# CM_FPGA_B2-3.net
KiCad netlist of a schematic drawn in Altium Designer
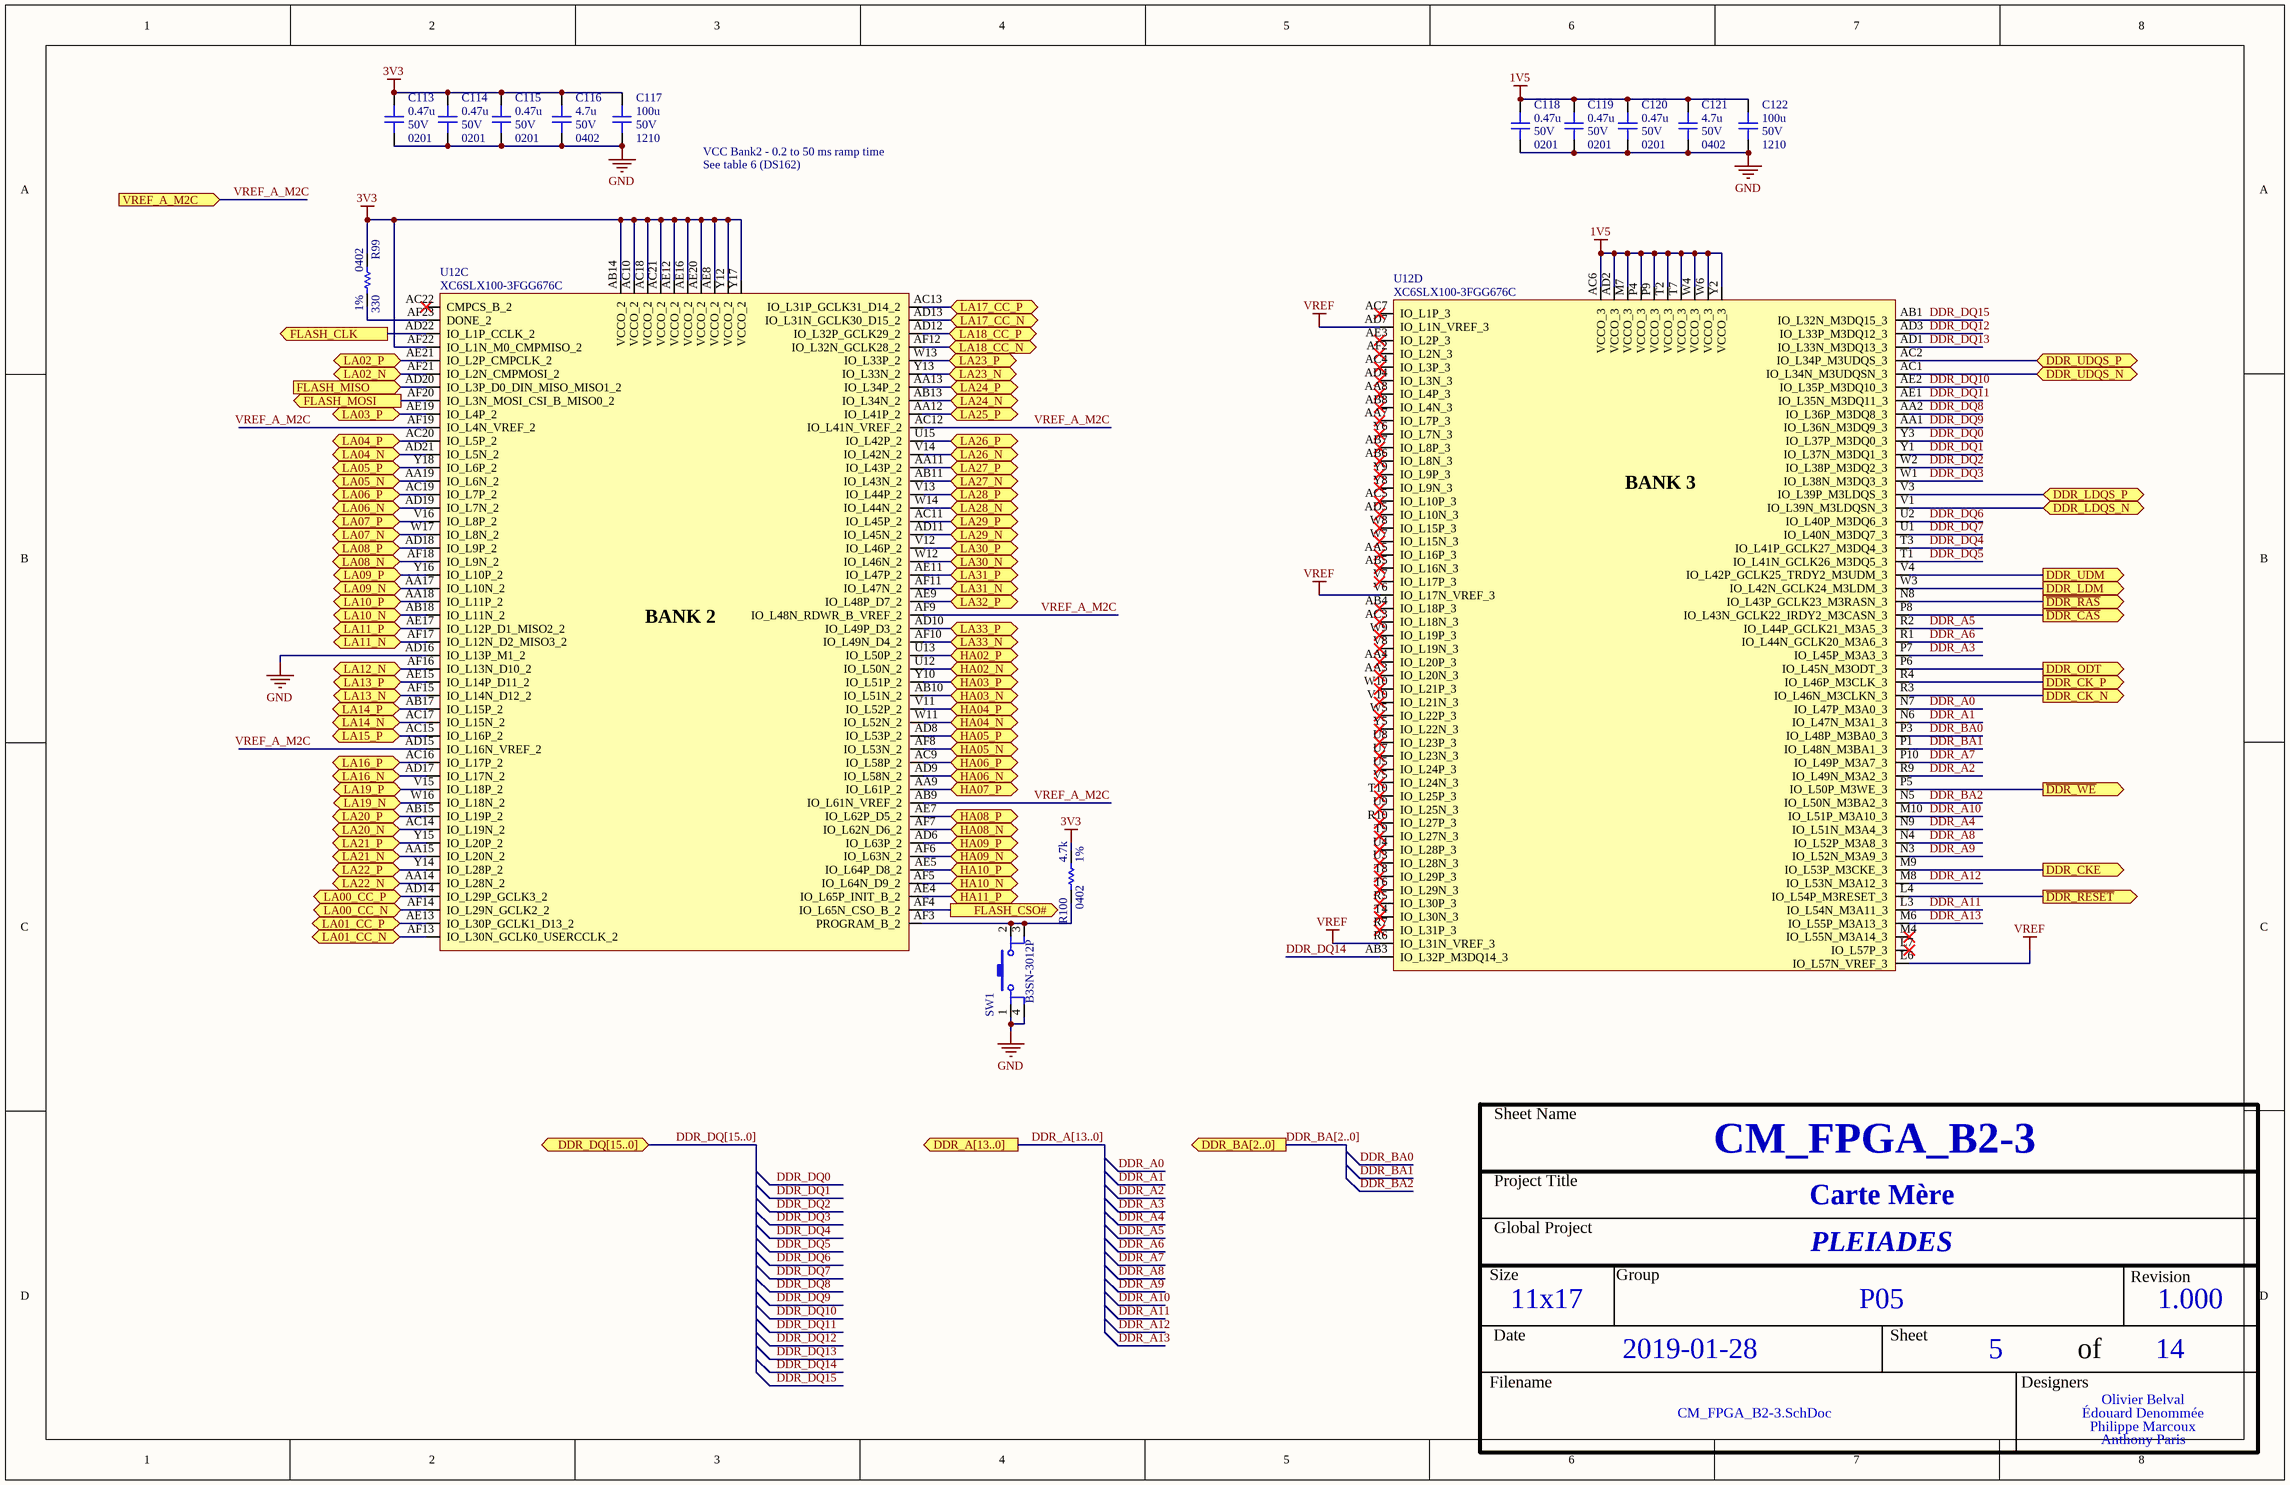
[diagram p0: CM_FPGA_B2-3.SchDoc]

(export (version "E")
  (design (tool "Eeschema 10.0.6"))
  (components
    (comp (ref "C113")
      (value "0.47u")
      (footprint "CAP_0201")
      (description "CAP - 0201")
      (fields
        (field (name "VOLTAGE") "50V")
        (field (name "PACKAGE") "0201")
        (field (name "CREATEDBY") "Jonathan Bouchard")
      )
      (libsource (lib "S7CAS_Lib2019_REV1_00") (part "CAP - 0201"))
    )
    (comp (ref "C114")
      (value "0.47u")
      (footprint "CAP_0201")
      (description "CAP - 0201")
      (fields
        (field (name "VOLTAGE") "50V")
        (field (name "PACKAGE") "0201")
        (field (name "CREATEDBY") "Jonathan Bouchard")
      )
      (libsource (lib "S7CAS_Lib2019_REV1_00") (part "CAP - 0201"))
    )
    (comp (ref "C115")
      (value "0.47u")
      (footprint "CAP_0201")
      (description "CAP - 0201")
      (fields
        (field (name "VOLTAGE") "50V")
        (field (name "PACKAGE") "0201")
        (field (name "CREATEDBY") "Jonathan Bouchard")
      )
      (libsource (lib "S7CAS_Lib2019_REV1_00") (part "CAP - 0201"))
    )
    (comp (ref "C116")
      (value "4.7u")
      (footprint "CAP_0402")
      (description "CAP - 0402")
      (fields
        (field (name "VOLTAGE") "50V")
        (field (name "PACKAGE") "0402")
        (field (name "CREATEDBY") "Jonathan Bouchard")
      )
      (libsource (lib "S7CAS_Lib2019_REV1_00") (part "CAP - 0402"))
    )
    (comp (ref "C117")
      (value "100u")
      (footprint "CAP_1210")
      (description "CAP - 1210")
      (fields
        (field (name "VOLTAGE") "50V")
        (field (name "PACKAGE") "1210")
        (field (name "CREATEDBY") "Jonathan Bouchard")
      )
      (libsource (lib "S7CAS_Lib2019_REV1_00") (part "CAP - 1210"))
    )
    (comp (ref "C118")
      (value "0.47u")
      (footprint "CAP_0201")
      (description "CAP - 0201")
      (fields
        (field (name "VOLTAGE") "50V")
        (field (name "PACKAGE") "0201")
        (field (name "CREATEDBY") "Jonathan Bouchard")
      )
      (libsource (lib "S7CAS_Lib2019_REV1_00") (part "CAP - 0201"))
    )
    (comp (ref "C119")
      (value "0.47u")
      (footprint "CAP_0201")
      (description "CAP - 0201")
      (fields
        (field (name "VOLTAGE") "50V")
        (field (name "PACKAGE") "0201")
        (field (name "CREATEDBY") "Jonathan Bouchard")
      )
      (libsource (lib "S7CAS_Lib2019_REV1_00") (part "CAP - 0201"))
    )
    (comp (ref "C120")
      (value "0.47u")
      (footprint "CAP_0201")
      (description "CAP - 0201")
      (fields
        (field (name "VOLTAGE") "50V")
        (field (name "PACKAGE") "0201")
        (field (name "CREATEDBY") "Jonathan Bouchard")
      )
      (libsource (lib "S7CAS_Lib2019_REV1_00") (part "CAP - 0201"))
    )
    (comp (ref "C121")
      (value "4.7u")
      (footprint "CAP_0402")
      (description "CAP - 0402")
      (fields
        (field (name "VOLTAGE") "50V")
        (field (name "PACKAGE") "0402")
        (field (name "CREATEDBY") "Jonathan Bouchard")
      )
      (libsource (lib "S7CAS_Lib2019_REV1_00") (part "CAP - 0402"))
    )
    (comp (ref "C122")
      (value "100u")
      (footprint "CAP_1210")
      (description "CAP - 1210")
      (fields
        (field (name "VOLTAGE") "50V")
        (field (name "PACKAGE") "1210")
        (field (name "CREATEDBY") "Jonathan Bouchard")
      )
      (libsource (lib "S7CAS_Lib2019_REV1_00") (part "CAP - 1210"))
    )
    (comp (ref "R99")
      (value "330")
      (footprint "RES_0402")
      (description "RES - 0402")
      (fields
        (field (name "VOLTAGE") "50V")
        (field (name "POWER") "1/16W")
        (field (name "PACKAGE") "0402")
        (field (name "PRECISION") "1%")
        (field (name "CREATEDBY") "Jonathan Bouchard")
      )
      (libsource (lib "S7CAS_Lib2019_REV1_00") (part "RES - 0402"))
    )
    (comp (ref "R100")
      (value "4.7k")
      (footprint "RES_0402")
      (description "RES - 0402")
      (fields
        (field (name "VOLTAGE") "50V")
        (field (name "POWER") "1/16W")
        (field (name "PACKAGE") "0402")
        (field (name "PRECISION") "1%")
        (field (name "CREATEDBY") "Jonathan Bouchard")
      )
      (libsource (lib "S7CAS_Lib2019_REV1_00") (part "RES - 0402"))
    )
    (comp (ref "SW1")
      (value "B3SN-3012P")
      (footprint "SWI_TACT_B3SN-3012P")
      (description "SWI - TACT SPST-NO 0.05A 24V - 4-SMD")
      (fields
        (field (name "MFG") "Omron")
        (field (name "VOLTAGE") "24V")
        (field (name "CREATEDBY") "Jonathan Bouchard")
      )
      (libsource (lib "S7CAS_Lib2019_REV1_00") (part "SWI_TACT_B3SN-3012P"))
    )
    (comp (ref "U12")
      (value "XC6SLX100-3FGG676C")
      (footprint "FPGA_XILINX_FGG676")
      (description "FPGA - XILINX SPARTAN 6 480 I/O - BGA-676")
      (fields
        (field (name "VOLTAGE") "1.14 V ~ 1.26 V")
        (field (name "MFG") "Xilinx")
        (field (name "CREATEDBY") "Jonathan Bouchard")
      )
      (libsource (lib "S7CAS_Lib2019_REV1_00") (part "FPGA_XC6SLX100-3FGG676C"))
    )
  )
  (nets
    (net (code "1") (name "/DDR_A0") (class "Default")
      (node (ref "U12") (pin "N7") (pinfunction "IO_L47P_M3A0_3_N7") (pintype "passive"))
    )
    (net (code "2") (name "/DDR_A1") (class "Default")
      (node (ref "U12") (pin "N6") (pinfunction "IO_L47N_M3A1_3_N6") (pintype "passive"))
    )
    (net (code "3") (name "/DDR_A2") (class "Default")
      (node (ref "U12") (pin "R9") (pinfunction "IO_L49N_M3A2_3_R9") (pintype "passive"))
    )
    (net (code "4") (name "/DDR_A3") (class "Default")
      (node (ref "U12") (pin "P7") (pinfunction "IO_L45P_M3A3_3_P7") (pintype "passive"))
    )
    (net (code "5") (name "/DDR_A4") (class "Default")
      (node (ref "U12") (pin "N9") (pinfunction "IO_L51N_M3A4_3_N9") (pintype "passive"))
    )
    (net (code "6") (name "/DDR_A5") (class "Default")
      (node (ref "U12") (pin "R2") (pinfunction "IO_L44P_GCLK21_M3A5_3_R2") (pintype "passive"))
    )
    (net (code "7") (name "/DDR_A6") (class "Default")
      (node (ref "U12") (pin "R1") (pinfunction "IO_L44N_GCLK20_M3A6_3_R1") (pintype "passive"))
    )
    (net (code "8") (name "/DDR_A7") (class "Default")
      (node (ref "U12") (pin "P10") (pinfunction "IO_L49P_M3A7_3_P10") (pintype "passive"))
    )
    (net (code "9") (name "/DDR_A8") (class "Default")
      (node (ref "U12") (pin "N4") (pinfunction "IO_L52P_M3A8_3_N4") (pintype "passive"))
    )
    (net (code "10") (name "/DDR_A9") (class "Default")
      (node (ref "U12") (pin "N3") (pinfunction "IO_L52N_M3A9_3_N3") (pintype "passive"))
    )
    (net (code "11") (name "/DDR_A10") (class "Default")
      (node (ref "U12") (pin "M10") (pinfunction "IO_L51P_M3A10_3_M10") (pintype "passive"))
    )
    (net (code "12") (name "/DDR_A11") (class "Default")
      (node (ref "U12") (pin "L3") (pinfunction "IO_L54N_M3A11_3_L3") (pintype "passive"))
    )
    (net (code "13") (name "/DDR_A12") (class "Default")
      (node (ref "U12") (pin "M8") (pinfunction "IO_L53N_M3A12_3_M8") (pintype "passive"))
    )
    (net (code "14") (name "/DDR_A13") (class "Default")
      (node (ref "U12") (pin "M6") (pinfunction "IO_L55P_M3A13_3_M6") (pintype "passive"))
    )
    (net (code "16") (name "/DDR_BA0") (class "Default")
      (node (ref "U12") (pin "P3") (pinfunction "IO_L48P_M3BA0_3_P3") (pintype "passive"))
    )
    (net (code "17") (name "/DDR_BA1") (class "Default")
      (node (ref "U12") (pin "P1") (pinfunction "IO_L48N_M3BA1_3_P1") (pintype "passive"))
    )
    (net (code "18") (name "/DDR_BA2") (class "Default")
      (node (ref "U12") (pin "N5") (pinfunction "IO_L50N_M3BA2_3_N5") (pintype "passive"))
    )
    (net (code "20") (name "/DDR_CAS") (class "Default")
      (node (ref "U12") (pin "P8") (pinfunction "IO_L43N_GCLK22_IRDY2_M3CASN_3_P8") (pintype "passive"))
    )
    (net (code "21") (name "/DDR_CKE") (class "Default")
      (node (ref "U12") (pin "M9") (pinfunction "IO_L53P_M3CKE_3_M9") (pintype "passive"))
    )
    (net (code "22") (name "/DDR_CK_N") (class "Default")
      (node (ref "U12") (pin "R3") (pinfunction "IO_L46N_M3CLKN_3_R3") (pintype "passive"))
    )
    (net (code "23") (name "/DDR_CK_P") (class "Default")
      (node (ref "U12") (pin "R4") (pinfunction "IO_L46P_M3CLK_3_R4") (pintype "passive"))
    )
    (net (code "24") (name "/DDR_DQ0") (class "Default")
      (node (ref "U12") (pin "Y3") (pinfunction "IO_L37P_M3DQ0_3_Y3") (pintype "passive"))
    )
    (net (code "25") (name "/DDR_DQ1") (class "Default")
      (node (ref "U12") (pin "Y1") (pinfunction "IO_L37N_M3DQ1_3_Y1") (pintype "passive"))
    )
    (net (code "26") (name "/DDR_DQ2") (class "Default")
      (node (ref "U12") (pin "W2") (pinfunction "IO_L38P_M3DQ2_3_W2") (pintype "passive"))
    )
    (net (code "27") (name "/DDR_DQ3") (class "Default")
      (node (ref "U12") (pin "W1") (pinfunction "IO_L38N_M3DQ3_3_W1") (pintype "passive"))
    )
    (net (code "28") (name "/DDR_DQ4") (class "Default")
      (node (ref "U12") (pin "T3") (pinfunction "IO_L41P_GCLK27_M3DQ4_3_T3") (pintype "passive"))
    )
    (net (code "29") (name "/DDR_DQ5") (class "Default")
      (node (ref "U12") (pin "T1") (pinfunction "IO_L41N_GCLK26_M3DQ5_3_T1") (pintype "passive"))
    )
    (net (code "30") (name "/DDR_DQ6") (class "Default")
      (node (ref "U12") (pin "U2") (pinfunction "IO_L40P_M3DQ6_3_U2") (pintype "passive"))
    )
    (net (code "31") (name "/DDR_DQ7") (class "Default")
      (node (ref "U12") (pin "U1") (pinfunction "IO_L40N_M3DQ7_3_U1") (pintype "passive"))
    )
    (net (code "32") (name "/DDR_DQ8") (class "Default")
      (node (ref "U12") (pin "AA2") (pinfunction "IO_L36P_M3DQ8_3_AA2") (pintype "passive"))
    )
    (net (code "33") (name "/DDR_DQ9") (class "Default")
      (node (ref "U12") (pin "AA1") (pinfunction "IO_L36N_M3DQ9_3_AA1") (pintype "passive"))
    )
    (net (code "34") (name "/DDR_DQ10") (class "Default")
      (node (ref "U12") (pin "AE2") (pinfunction "IO_L35P_M3DQ10_3_AE2") (pintype "passive"))
    )
    (net (code "35") (name "/DDR_DQ11") (class "Default")
      (node (ref "U12") (pin "AE1") (pinfunction "IO_L35N_M3DQ11_3_AE1") (pintype "passive"))
    )
    (net (code "36") (name "/DDR_DQ12") (class "Default")
      (node (ref "U12") (pin "AD3") (pinfunction "IO_L33P_M3DQ12_3_AD3") (pintype "passive"))
    )
    (net (code "37") (name "/DDR_DQ13") (class "Default")
      (node (ref "U12") (pin "AD1") (pinfunction "IO_L33N_M3DQ13_3_AD1") (pintype "passive"))
    )
    (net (code "38") (name "/DDR_DQ14") (class "Default")
      (node (ref "U12") (pin "AB3") (pinfunction "IO_L32P_M3DQ14_3_AB3") (pintype "passive"))
    )
    (net (code "39") (name "/DDR_DQ15") (class "Default")
      (node (ref "U12") (pin "AB1") (pinfunction "IO_L32N_M3DQ15_3_AB1") (pintype "passive"))
    )
    (net (code "41") (name "/DDR_LDM") (class "Default")
      (node (ref "U12") (pin "W3") (pinfunction "IO_L42N_GCLK24_M3LDM_3_W3") (pintype "passive"))
    )
    (net (code "42") (name "/DDR_LDQS_N") (class "Default")
      (node (ref "U12") (pin "V1") (pinfunction "IO_L39N_M3LDQSN_3_V1") (pintype "passive"))
    )
    (net (code "43") (name "/DDR_LDQS_P") (class "Default")
      (node (ref "U12") (pin "V3") (pinfunction "IO_L39P_M3LDQS_3_V3") (pintype "passive"))
    )
    (net (code "44") (name "/DDR_ODT") (class "Default")
      (node (ref "U12") (pin "P6") (pinfunction "IO_L45N_M3ODT_3_P6") (pintype "passive"))
    )
    (net (code "45") (name "/DDR_RAS") (class "Default")
      (node (ref "U12") (pin "N8") (pinfunction "IO_L43P_GCLK23_M3RASN_3_N8") (pintype "passive"))
    )
    (net (code "46") (name "/DDR_RESET") (class "Default")
      (node (ref "U12") (pin "L4") (pinfunction "IO_L54P_M3RESET_3_L4") (pintype "passive"))
    )
    (net (code "47") (name "/DDR_UDM") (class "Default")
      (node (ref "U12") (pin "V4") (pinfunction "IO_L42P_GCLK25_TRDY2_M3UDM_3_V4") (pintype "passive"))
    )
    (net (code "48") (name "/DDR_UDQS_N") (class "Default")
      (node (ref "U12") (pin "AC1") (pinfunction "IO_L34N_M3UDQSN_3_AC1") (pintype "passive"))
    )
    (net (code "49") (name "/DDR_UDQS_P") (class "Default")
      (node (ref "U12") (pin "AC2") (pinfunction "IO_L34P_M3UDQS_3_AC2") (pintype "passive"))
    )
    (net (code "50") (name "/DDR_WE") (class "Default")
      (node (ref "U12") (pin "P5") (pinfunction "IO_L50P_M3WE_3_P5") (pintype "passive"))
    )
    (net (code "51") (name "/FLASH_CLK") (class "Default")
      (node (ref "U12") (pin "AD22") (pinfunction "IO_L1P_CCLK_2_AD22") (pintype "passive"))
    )
    (net (code "52") (name "/FLASH_CSO#") (class "Default")
      (node (ref "U12") (pin "AF4") (pinfunction "IO_L65N_CSO_B_2_AF4") (pintype "passive"))
    )
    (net (code "53") (name "/FLASH_MISO") (class "Default")
      (node (ref "U12") (pin "AD20") (pinfunction "IO_L3P_D0_DIN_MISO_MISO1_2_AD20") (pintype "passive"))
    )
    (net (code "54") (name "/FLASH_MOSI") (class "Default")
      (node (ref "U12") (pin "AF20") (pinfunction "IO_L3N_MOSI_CSI_B_MISO0_2_AF20") (pintype "passive"))
    )
    (net (code "55") (name "/HA02_N") (class "Default")
      (node (ref "U12") (pin "U12") (pinfunction "IO_L50N_2_U12") (pintype "passive"))
    )
    (net (code "56") (name "/HA02_P") (class "Default")
      (node (ref "U12") (pin "U13") (pinfunction "IO_L50P_2_U13") (pintype "passive"))
    )
    (net (code "57") (name "/HA03_N") (class "Default")
      (node (ref "U12") (pin "AB10") (pinfunction "IO_L51N_2_AB10") (pintype "passive"))
    )
    (net (code "58") (name "/HA03_P") (class "Default")
      (node (ref "U12") (pin "Y10") (pinfunction "IO_L51P_2_Y10") (pintype "passive"))
    )
    (net (code "59") (name "/HA04_N") (class "Default")
      (node (ref "U12") (pin "W11") (pinfunction "IO_L52N_2_W11") (pintype "passive"))
    )
    (net (code "60") (name "/HA04_P") (class "Default")
      (node (ref "U12") (pin "V11") (pinfunction "IO_L52P_2_V11") (pintype "passive"))
    )
    (net (code "61") (name "/HA05_N") (class "Default")
      (node (ref "U12") (pin "AF8") (pinfunction "IO_L53N_2_AF8") (pintype "passive"))
    )
    (net (code "62") (name "/HA05_P") (class "Default")
      (node (ref "U12") (pin "AD8") (pinfunction "IO_L53P_2_AD8") (pintype "passive"))
    )
    (net (code "63") (name "/HA06_N") (class "Default")
      (node (ref "U12") (pin "AD9") (pinfunction "IO_L58N_2_AD9") (pintype "passive"))
    )
    (net (code "64") (name "/HA06_P") (class "Default")
      (node (ref "U12") (pin "AC9") (pinfunction "IO_L58P_2_AC9") (pintype "passive"))
    )
    (net (code "65") (name "/HA07_P") (class "Default")
      (node (ref "U12") (pin "AA9") (pinfunction "IO_L61P_2_AA9") (pintype "passive"))
    )
    (net (code "66") (name "/HA08_N") (class "Default")
      (node (ref "U12") (pin "AF7") (pinfunction "IO_L62N_D6_2_AF7") (pintype "passive"))
    )
    (net (code "67") (name "/HA08_P") (class "Default")
      (node (ref "U12") (pin "AE7") (pinfunction "IO_L62P_D5_2_AE7") (pintype "passive"))
    )
    (net (code "68") (name "/HA09_N") (class "Default")
      (node (ref "U12") (pin "AF6") (pinfunction "IO_L63N_2_AF6") (pintype "passive"))
    )
    (net (code "69") (name "/HA09_P") (class "Default")
      (node (ref "U12") (pin "AD6") (pinfunction "IO_L63P_2_AD6") (pintype "passive"))
    )
    (net (code "70") (name "/HA10_N") (class "Default")
      (node (ref "U12") (pin "AF5") (pinfunction "IO_L64N_D9_2_AF5") (pintype "passive"))
    )
    (net (code "71") (name "/HA10_P") (class "Default")
      (node (ref "U12") (pin "AE5") (pinfunction "IO_L64P_D8_2_AE5") (pintype "passive"))
    )
    (net (code "72") (name "/HA11_P") (class "Default")
      (node (ref "U12") (pin "AE4") (pinfunction "IO_L65P_INIT_B_2_AE4") (pintype "passive"))
    )
    (net (code "73") (name "/LA00_CC_N") (class "Default")
      (node (ref "U12") (pin "AF14") (pinfunction "IO_L29N_GCLK2_2_AF14") (pintype "passive"))
    )
    (net (code "74") (name "/LA00_CC_P") (class "Default")
      (node (ref "U12") (pin "AD14") (pinfunction "IO_L29P_GCLK3_2_AD14") (pintype "passive"))
    )
    (net (code "75") (name "/LA01_CC_N") (class "Default")
      (node (ref "U12") (pin "AF13") (pinfunction "IO_L30N_GCLK0_USERCCLK_2_AF13") (pintype "passive"))
    )
    (net (code "76") (name "/LA01_CC_P") (class "Default")
      (node (ref "U12") (pin "AE13") (pinfunction "IO_L30P_GCLK1_D13_2_AE13") (pintype "passive"))
    )
    (net (code "77") (name "/LA02_N") (class "Default")
      (node (ref "U12") (pin "AF21") (pinfunction "IO_L2N_CMPMOSI_2_AF21") (pintype "passive"))
    )
    (net (code "78") (name "/LA02_P") (class "Default")
      (node (ref "U12") (pin "AE21") (pinfunction "IO_L2P_CMPCLK_2_AE21") (pintype "passive"))
    )
    (net (code "79") (name "/LA03_P") (class "Default")
      (node (ref "U12") (pin "AE19") (pinfunction "IO_L4P_2_AE19") (pintype "passive"))
    )
    (net (code "80") (name "/LA04_N") (class "Default")
      (node (ref "U12") (pin "AD21") (pinfunction "IO_L5N_2_AD21") (pintype "passive"))
    )
    (net (code "81") (name "/LA04_P") (class "Default")
      (node (ref "U12") (pin "AC20") (pinfunction "IO_L5P_2_AC20") (pintype "passive"))
    )
    (net (code "82") (name "/LA05_N") (class "Default")
      (node (ref "U12") (pin "AA19") (pinfunction "IO_L6N_2_AA19") (pintype "passive"))
    )
    (net (code "83") (name "/LA05_P") (class "Default")
      (node (ref "U12") (pin "Y18") (pinfunction "IO_L6P_2_Y18") (pintype "passive"))
    )
    (net (code "84") (name "/LA06_N") (class "Default")
      (node (ref "U12") (pin "AD19") (pinfunction "IO_L7N_2_AD19") (pintype "passive"))
    )
    (net (code "85") (name "/LA06_P") (class "Default")
      (node (ref "U12") (pin "AC19") (pinfunction "IO_L7P_2_AC19") (pintype "passive"))
    )
    (net (code "86") (name "/LA07_N") (class "Default")
      (node (ref "U12") (pin "W17") (pinfunction "IO_L8N_2_W17") (pintype "passive"))
    )
    (net (code "87") (name "/LA07_P") (class "Default")
      (node (ref "U12") (pin "V16") (pinfunction "IO_L8P_2_V16") (pintype "passive"))
    )
    (net (code "88") (name "/LA08_N") (class "Default")
      (node (ref "U12") (pin "AF18") (pinfunction "IO_L9N_2_AF18") (pintype "passive"))
    )
    (net (code "89") (name "/LA08_P") (class "Default")
      (node (ref "U12") (pin "AD18") (pinfunction "IO_L9P_2_AD18") (pintype "passive"))
    )
    (net (code "90") (name "/LA09_N") (class "Default")
      (node (ref "U12") (pin "AA17") (pinfunction "IO_L10N_2_AA17") (pintype "passive"))
    )
    (net (code "91") (name "/LA09_P") (class "Default")
      (node (ref "U12") (pin "Y16") (pinfunction "IO_L10P_2_Y16") (pintype "passive"))
    )
    (net (code "92") (name "/LA10_N") (class "Default")
      (node (ref "U12") (pin "AB18") (pinfunction "IO_L11N_2_AB18") (pintype "passive"))
    )
    (net (code "93") (name "/LA10_P") (class "Default")
      (node (ref "U12") (pin "AA18") (pinfunction "IO_L11P_2_AA18") (pintype "passive"))
    )
    (net (code "94") (name "/LA11_N") (class "Default")
      (node (ref "U12") (pin "AF17") (pinfunction "IO_L12N_D2_MISO3_2_AF17") (pintype "passive"))
    )
    (net (code "95") (name "/LA11_P") (class "Default")
      (node (ref "U12") (pin "AE17") (pinfunction "IO_L12P_D1_MISO2_2_AE17") (pintype "passive"))
    )
    (net (code "96") (name "/LA12_N") (class "Default")
      (node (ref "U12") (pin "AF16") (pinfunction "IO_L13N_D10_2_AF16") (pintype "passive"))
    )
    (net (code "97") (name "/LA13_N") (class "Default")
      (node (ref "U12") (pin "AF15") (pinfunction "IO_L14N_D12_2_AF15") (pintype "passive"))
    )
    (net (code "98") (name "/LA13_P") (class "Default")
      (node (ref "U12") (pin "AE15") (pinfunction "IO_L14P_D11_2_AE15") (pintype "passive"))
    )
    (net (code "99") (name "/LA14_N") (class "Default")
      (node (ref "U12") (pin "AC17") (pinfunction "IO_L15N_2_AC17") (pintype "passive"))
    )
    (net (code "100") (name "/LA14_P") (class "Default")
      (node (ref "U12") (pin "AB17") (pinfunction "IO_L15P_2_AB17") (pintype "passive"))
    )
    (net (code "101") (name "/LA15_P") (class "Default")
      (node (ref "U12") (pin "AC15") (pinfunction "IO_L16P_2_AC15") (pintype "passive"))
    )
    (net (code "102") (name "/LA16_N") (class "Default")
      (node (ref "U12") (pin "AD17") (pinfunction "IO_L17N_2_AD17") (pintype "passive"))
    )
    (net (code "103") (name "/LA16_P") (class "Default")
      (node (ref "U12") (pin "AC16") (pinfunction "IO_L17P_2_AC16") (pintype "passive"))
    )
    (net (code "104") (name "/LA17_CC_N") (class "Default")
      (node (ref "U12") (pin "AD13") (pinfunction "IO_L31N_GCLK30_D15_2_AD13") (pintype "passive"))
    )
    (net (code "105") (name "/LA17_CC_P") (class "Default")
      (node (ref "U12") (pin "AC13") (pinfunction "IO_L31P_GCLK31_D14_2_AC13") (pintype "passive"))
    )
    (net (code "106") (name "/LA18_CC_N") (class "Default")
      (node (ref "U12") (pin "AF12") (pinfunction "IO_L32N_GCLK28_2_AF12") (pintype "passive"))
    )
    (net (code "107") (name "/LA18_CC_P") (class "Default")
      (node (ref "U12") (pin "AD12") (pinfunction "IO_L32P_GCLK29_2_AD12") (pintype "passive"))
    )
    (net (code "108") (name "/LA19_N") (class "Default")
      (node (ref "U12") (pin "W16") (pinfunction "IO_L18N_2_W16") (pintype "passive"))
    )
    (net (code "109") (name "/LA19_P") (class "Default")
      (node (ref "U12") (pin "V15") (pinfunction "IO_L18P_2_V15") (pintype "passive"))
    )
    (net (code "110") (name "/LA20_N") (class "Default")
      (node (ref "U12") (pin "AC14") (pinfunction "IO_L19N_2_AC14") (pintype "passive"))
    )
    (net (code "111") (name "/LA20_P") (class "Default")
      (node (ref "U12") (pin "AB15") (pinfunction "IO_L19P_2_AB15") (pintype "passive"))
    )
    (net (code "112") (name "/LA21_N") (class "Default")
      (node (ref "U12") (pin "AA15") (pinfunction "IO_L20N_2_AA15") (pintype "passive"))
    )
    (net (code "113") (name "/LA21_P") (class "Default")
      (node (ref "U12") (pin "Y15") (pinfunction "IO_L20P_2_Y15") (pintype "passive"))
    )
    (net (code "114") (name "/LA22_N") (class "Default")
      (node (ref "U12") (pin "AA14") (pinfunction "IO_L28N_2_AA14") (pintype "passive"))
    )
    (net (code "115") (name "/LA22_P") (class "Default")
      (node (ref "U12") (pin "Y14") (pinfunction "IO_L28P_2_Y14") (pintype "passive"))
    )
    (net (code "116") (name "/LA23_N") (class "Default")
      (node (ref "U12") (pin "Y13") (pinfunction "IO_L33N_2_Y13") (pintype "passive"))
    )
    (net (code "117") (name "/LA23_P") (class "Default")
      (node (ref "U12") (pin "W13") (pinfunction "IO_L33P_2_W13") (pintype "passive"))
    )
    (net (code "118") (name "/LA24_N") (class "Default")
      (node (ref "U12") (pin "AB13") (pinfunction "IO_L34N_2_AB13") (pintype "passive"))
    )
    (net (code "119") (name "/LA24_P") (class "Default")
      (node (ref "U12") (pin "AA13") (pinfunction "IO_L34P_2_AA13") (pintype "passive"))
    )
    (net (code "120") (name "/LA25_P") (class "Default")
      (node (ref "U12") (pin "AA12") (pinfunction "IO_L41P_2_AA12") (pintype "passive"))
    )
    (net (code "121") (name "/LA26_N") (class "Default")
      (node (ref "U12") (pin "V14") (pinfunction "IO_L42N_2_V14") (pintype "passive"))
    )
    (net (code "122") (name "/LA26_P") (class "Default")
      (node (ref "U12") (pin "U15") (pinfunction "IO_L42P_2_U15") (pintype "passive"))
    )
    (net (code "123") (name "/LA27_N") (class "Default")
      (node (ref "U12") (pin "AB11") (pinfunction "IO_L43N_2_AB11") (pintype "passive"))
    )
    (net (code "124") (name "/LA27_P") (class "Default")
      (node (ref "U12") (pin "AA11") (pinfunction "IO_L43P_2_AA11") (pintype "passive"))
    )
    (net (code "125") (name "/LA28_N") (class "Default")
      (node (ref "U12") (pin "W14") (pinfunction "IO_L44N_2_W14") (pintype "passive"))
    )
    (net (code "126") (name "/LA28_P") (class "Default")
      (node (ref "U12") (pin "V13") (pinfunction "IO_L44P_2_V13") (pintype "passive"))
    )
    (net (code "127") (name "/LA29_N") (class "Default")
      (node (ref "U12") (pin "AD11") (pinfunction "IO_L45N_2_AD11") (pintype "passive"))
    )
    (net (code "128") (name "/LA29_P") (class "Default")
      (node (ref "U12") (pin "AC11") (pinfunction "IO_L45P_2_AC11") (pintype "passive"))
    )
    (net (code "129") (name "/LA30_N") (class "Default")
      (node (ref "U12") (pin "W12") (pinfunction "IO_L46N_2_W12") (pintype "passive"))
    )
    (net (code "130") (name "/LA30_P") (class "Default")
      (node (ref "U12") (pin "V12") (pinfunction "IO_L46P_2_V12") (pintype "passive"))
    )
    (net (code "131") (name "/LA31_N") (class "Default")
      (node (ref "U12") (pin "AF11") (pinfunction "IO_L47N_2_AF11") (pintype "passive"))
    )
    (net (code "132") (name "/LA31_P") (class "Default")
      (node (ref "U12") (pin "AE11") (pinfunction "IO_L47P_2_AE11") (pintype "passive"))
    )
    (net (code "133") (name "/LA32_P") (class "Default")
      (node (ref "U12") (pin "AE9") (pinfunction "IO_L48P_D7_2_AE9") (pintype "passive"))
    )
    (net (code "134") (name "/LA33_N") (class "Default")
      (node (ref "U12") (pin "AF10") (pinfunction "IO_L49N_D4_2_AF10") (pintype "passive"))
    )
    (net (code "135") (name "/LA33_P") (class "Default")
      (node (ref "U12") (pin "AD10") (pinfunction "IO_L49P_D3_2_AD10") (pintype "passive"))
    )
    (net (code "136") (name "/VREF_A_M2C") (class "Default")
      (node (ref "U12") (pin "AB9") (pinfunction "IO_L61N_VREF_2_AB9") (pintype "passive"))
      (node (ref "U12") (pin "AC12") (pinfunction "IO_L41N_VREF_2_AC12") (pintype "passive"))
      (node (ref "U12") (pin "AD15") (pinfunction "IO_L16N_VREF_2_AD15") (pintype "passive"))
      (node (ref "U12") (pin "AF19") (pinfunction "IO_L4N_VREF_2_AF19") (pintype "passive"))
      (node (ref "U12") (pin "AF9") (pinfunction "IO_L48N_RDWR_B_VREF_2_AF9") (pintype "passive"))
    )
    (net (code "137") (name "1V5") (class "Default")
      (node (ref "C118") (pin "2") (pinfunction "2_2") (pintype "passive"))
      (node (ref "C119") (pin "2") (pinfunction "2_2") (pintype "passive"))
      (node (ref "C120") (pin "2") (pinfunction "2_2") (pintype "passive"))
      (node (ref "C121") (pin "2") (pinfunction "2_2") (pintype "passive"))
      (node (ref "C122") (pin "2") (pinfunction "2_2") (pintype "passive"))
      (node (ref "U12") (pin "AC6") (pinfunction "VCCO_3_AC6") (pintype "passive"))
      (node (ref "U12") (pin "AD2") (pinfunction "VCCO_3_AD2") (pintype "passive"))
      (node (ref "U12") (pin "M7") (pinfunction "VCCO_3_M7") (pintype "passive"))
      (node (ref "U12") (pin "P4") (pinfunction "VCCO_3_P4") (pintype "passive"))
      (node (ref "U12") (pin "P9") (pinfunction "VCCO_3_P9") (pintype "passive"))
      (node (ref "U12") (pin "T2") (pinfunction "VCCO_3_T2") (pintype "passive"))
      (node (ref "U12") (pin "T7") (pinfunction "VCCO_3_T7") (pintype "passive"))
      (node (ref "U12") (pin "W4") (pinfunction "VCCO_3_W4") (pintype "passive"))
      (node (ref "U12") (pin "W6") (pinfunction "VCCO_3_W6") (pintype "passive"))
      (node (ref "U12") (pin "Y2") (pinfunction "VCCO_3_Y2") (pintype "passive"))
    )
    (net (code "138") (name "3V3") (class "Default")
      (node (ref "C113") (pin "2") (pinfunction "2_2") (pintype "passive"))
      (node (ref "C114") (pin "2") (pinfunction "2_2") (pintype "passive"))
      (node (ref "C115") (pin "2") (pinfunction "2_2") (pintype "passive"))
      (node (ref "C116") (pin "2") (pinfunction "2_2") (pintype "passive"))
      (node (ref "C117") (pin "2") (pinfunction "2_2") (pintype "passive"))
      (node (ref "R100") (pin "2") (pinfunction "2_2") (pintype "passive"))
      (node (ref "R99") (pin "1") (pinfunction "1_1") (pintype "passive"))
      (node (ref "U12") (pin "AB14") (pinfunction "VCCO_2_AB14") (pintype "passive"))
      (node (ref "U12") (pin "AC10") (pinfunction "VCCO_2_AC10") (pintype "passive"))
      (node (ref "U12") (pin "AC18") (pinfunction "VCCO_2_AC18") (pintype "passive"))
      (node (ref "U12") (pin "AC21") (pinfunction "VCCO_2_AC21") (pintype "passive"))
      (node (ref "U12") (pin "AE12") (pinfunction "VCCO_2_AE12") (pintype "passive"))
      (node (ref "U12") (pin "AE16") (pinfunction "VCCO_2_AE16") (pintype "passive"))
      (node (ref "U12") (pin "AE20") (pinfunction "VCCO_2_AE20") (pintype "passive"))
      (node (ref "U12") (pin "AE8") (pinfunction "VCCO_2_AE8") (pintype "passive"))
      (node (ref "U12") (pin "AF22") (pinfunction "IO_L1N_M0_CMPMISO_2_AF22") (pintype "passive"))
      (node (ref "U12") (pin "Y12") (pinfunction "VCCO_2_Y12") (pintype "passive"))
      (node (ref "U12") (pin "Y17") (pinfunction "VCCO_2_Y17") (pintype "passive"))
    )
    (net (code "139") (name "GND") (class "Default")
      (node (ref "C113") (pin "1") (pinfunction "1_1") (pintype "passive"))
      (node (ref "C114") (pin "1") (pinfunction "1_1") (pintype "passive"))
      (node (ref "C115") (pin "1") (pinfunction "1_1") (pintype "passive"))
      (node (ref "C116") (pin "1") (pinfunction "1_1") (pintype "passive"))
      (node (ref "C117") (pin "1") (pinfunction "1_1") (pintype "passive"))
      (node (ref "C118") (pin "1") (pinfunction "1_1") (pintype "passive"))
      (node (ref "C119") (pin "1") (pinfunction "1_1") (pintype "passive"))
      (node (ref "C120") (pin "1") (pinfunction "1_1") (pintype "passive"))
      (node (ref "C121") (pin "1") (pinfunction "1_1") (pintype "passive"))
      (node (ref "C122") (pin "1") (pinfunction "1_1") (pintype "passive"))
      (node (ref "SW1") (pin "1") (pinfunction "1_1") (pintype "passive"))
      (node (ref "SW1") (pin "4") (pinfunction "4_4") (pintype "passive"))
      (node (ref "U12") (pin "AD16") (pinfunction "IO_L13P_M1_2_AD16") (pintype "passive"))
    )
    (net (code "140") (name "Net-(U12C-DONE_2)") (class "Default")
      (node (ref "R99") (pin "2") (pinfunction "2_2") (pintype "passive"))
      (node (ref "U12") (pin "AF23") (pinfunction "DONE_2_AF23") (pintype "passive"))
    )
    (net (code "141") (name "Net-(U12C-PROGRAM_B_2)") (class "Default")
      (node (ref "R100") (pin "1") (pinfunction "1_1") (pintype "passive"))
      (node (ref "SW1") (pin "2") (pinfunction "2_2") (pintype "passive"))
      (node (ref "SW1") (pin "3") (pinfunction "3_3") (pintype "passive"))
      (node (ref "U12") (pin "AF3") (pinfunction "PROGRAM_B_2_AF3") (pintype "passive"))
    )
    (net (code "142") (name "VREF") (class "Default")
      (node (ref "U12") (pin "AD7") (pinfunction "IO_L1N_VREF_3_AD7") (pintype "passive"))
      (node (ref "U12") (pin "L6") (pinfunction "IO_L57N_VREF_3_L6") (pintype "passive"))
      (node (ref "U12") (pin "R6") (pinfunction "IO_L31N_VREF_3_R6") (pintype "passive"))
      (node (ref "U12") (pin "V6") (pinfunction "IO_L17N_VREF_3_V6") (pintype "passive"))
    )
    (net (code "143") (name "unconnected-(U12C-CMPCS_B_2-PadAC22)") (class "Default")
      (node (ref "U12") (pin "AC22") (pinfunction "CMPCS_B_2_AC22") (pintype "passive+no_connect"))
    )
    (net (code "144") (name "unconnected-(U12D-IO_L1P_3-PadAC7)") (class "Default")
      (node (ref "U12") (pin "AC7") (pinfunction "IO_L1P_3_AC7") (pintype "passive+no_connect"))
    )
    (net (code "145") (name "unconnected-(U12D-IO_L2N_3-PadAF2)") (class "Default")
      (node (ref "U12") (pin "AF2") (pinfunction "IO_L2N_3_AF2") (pintype "passive+no_connect"))
    )
    (net (code "146") (name "unconnected-(U12D-IO_L2P_3-PadAE3)") (class "Default")
      (node (ref "U12") (pin "AE3") (pinfunction "IO_L2P_3_AE3") (pintype "passive+no_connect"))
    )
    (net (code "147") (name "unconnected-(U12D-IO_L3N_3-PadAD4)") (class "Default")
      (node (ref "U12") (pin "AD4") (pinfunction "IO_L3N_3_AD4") (pintype "passive+no_connect"))
    )
    (net (code "148") (name "unconnected-(U12D-IO_L3P_3-PadAC4)") (class "Default")
      (node (ref "U12") (pin "AC4") (pinfunction "IO_L3P_3_AC4") (pintype "passive+no_connect"))
    )
    (net (code "149") (name "unconnected-(U12D-IO_L4N_3-PadAB8)") (class "Default")
      (node (ref "U12") (pin "AB8") (pinfunction "IO_L4N_3_AB8") (pintype "passive+no_connect"))
    )
    (net (code "150") (name "unconnected-(U12D-IO_L4P_3-PadAA8)") (class "Default")
      (node (ref "U12") (pin "AA8") (pinfunction "IO_L4P_3_AA8") (pintype "passive+no_connect"))
    )
    (net (code "151") (name "unconnected-(U12D-IO_L7N_3-PadY6)") (class "Default")
      (node (ref "U12") (pin "Y6") (pinfunction "IO_L7N_3_Y6") (pintype "passive+no_connect"))
    )
    (net (code "152") (name "unconnected-(U12D-IO_L7P_3-PadAA7)") (class "Default")
      (node (ref "U12") (pin "AA7") (pinfunction "IO_L7P_3_AA7") (pintype "passive+no_connect"))
    )
    (net (code "153") (name "unconnected-(U12D-IO_L8N_3-PadAB6)") (class "Default")
      (node (ref "U12") (pin "AB6") (pinfunction "IO_L8N_3_AB6") (pintype "passive+no_connect"))
    )
    (net (code "154") (name "unconnected-(U12D-IO_L8P_3-PadAB7)") (class "Default")
      (node (ref "U12") (pin "AB7") (pinfunction "IO_L8P_3_AB7") (pintype "passive+no_connect"))
    )
    (net (code "155") (name "unconnected-(U12D-IO_L9N_3-PadY8)") (class "Default")
      (node (ref "U12") (pin "Y8") (pinfunction "IO_L9N_3_Y8") (pintype "passive+no_connect"))
    )
    (net (code "156") (name "unconnected-(U12D-IO_L9P_3-PadY9)") (class "Default")
      (node (ref "U12") (pin "Y9") (pinfunction "IO_L9P_3_Y9") (pintype "passive+no_connect"))
    )
    (net (code "157") (name "unconnected-(U12D-IO_L10N_3-PadAD5)") (class "Default")
      (node (ref "U12") (pin "AD5") (pinfunction "IO_L10N_3_AD5") (pintype "passive+no_connect"))
    )
    (net (code "158") (name "unconnected-(U12D-IO_L10P_3-PadAC5)") (class "Default")
      (node (ref "U12") (pin "AC5") (pinfunction "IO_L10P_3_AC5") (pintype "passive+no_connect"))
    )
    (net (code "159") (name "unconnected-(U12D-IO_L15N_3-PadW7)") (class "Default")
      (node (ref "U12") (pin "W7") (pinfunction "IO_L15N_3_W7") (pintype "passive+no_connect"))
    )
    (net (code "160") (name "unconnected-(U12D-IO_L15P_3-PadW8)") (class "Default")
      (node (ref "U12") (pin "W8") (pinfunction "IO_L15P_3_W8") (pintype "passive+no_connect"))
    )
    (net (code "161") (name "unconnected-(U12D-IO_L16N_3-PadAB5)") (class "Default")
      (node (ref "U12") (pin "AB5") (pinfunction "IO_L16N_3_AB5") (pintype "passive+no_connect"))
    )
    (net (code "162") (name "unconnected-(U12D-IO_L16P_3-PadAA5)") (class "Default")
      (node (ref "U12") (pin "AA5") (pinfunction "IO_L16P_3_AA5") (pintype "passive+no_connect"))
    )
    (net (code "163") (name "unconnected-(U12D-IO_L17P_3-PadV7)") (class "Default")
      (node (ref "U12") (pin "V7") (pinfunction "IO_L17P_3_V7") (pintype "passive+no_connect"))
    )
    (net (code "164") (name "unconnected-(U12D-IO_L18N_3-PadAC3)") (class "Default")
      (node (ref "U12") (pin "AC3") (pinfunction "IO_L18N_3_AC3") (pintype "passive+no_connect"))
    )
    (net (code "165") (name "unconnected-(U12D-IO_L18P_3-PadAB4)") (class "Default")
      (node (ref "U12") (pin "AB4") (pinfunction "IO_L18P_3_AB4") (pintype "passive+no_connect"))
    )
    (net (code "166") (name "unconnected-(U12D-IO_L19N_3-PadV8)") (class "Default")
      (node (ref "U12") (pin "V8") (pinfunction "IO_L19N_3_V8") (pintype "passive+no_connect"))
    )
    (net (code "167") (name "unconnected-(U12D-IO_L19P_3-PadW9)") (class "Default")
      (node (ref "U12") (pin "W9") (pinfunction "IO_L19P_3_W9") (pintype "passive+no_connect"))
    )
    (net (code "168") (name "unconnected-(U12D-IO_L20N_3-PadAA3)") (class "Default")
      (node (ref "U12") (pin "AA3") (pinfunction "IO_L20N_3_AA3") (pintype "passive+no_connect"))
    )
    (net (code "169") (name "unconnected-(U12D-IO_L20P_3-PadAA4)") (class "Default")
      (node (ref "U12") (pin "AA4") (pinfunction "IO_L20P_3_AA4") (pintype "passive+no_connect"))
    )
    (net (code "170") (name "unconnected-(U12D-IO_L21N_3-PadV10)") (class "Default")
      (node (ref "U12") (pin "V10") (pinfunction "IO_L21N_3_V10") (pintype "passive+no_connect"))
    )
    (net (code "171") (name "unconnected-(U12D-IO_L21P_3-PadW10)") (class "Default")
      (node (ref "U12") (pin "W10") (pinfunction "IO_L21P_3_W10") (pintype "passive+no_connect"))
    )
    (net (code "172") (name "unconnected-(U12D-IO_L22N_3-PadY5)") (class "Default")
      (node (ref "U12") (pin "Y5") (pinfunction "IO_L22N_3_Y5") (pintype "passive+no_connect"))
    )
    (net (code "173") (name "unconnected-(U12D-IO_L22P_3-PadW5)") (class "Default")
      (node (ref "U12") (pin "W5") (pinfunction "IO_L22P_3_W5") (pintype "passive+no_connect"))
    )
    (net (code "174") (name "unconnected-(U12D-IO_L23N_3-PadU7)") (class "Default")
      (node (ref "U12") (pin "U7") (pinfunction "IO_L23N_3_U7") (pintype "passive+no_connect"))
    )
    (net (code "175") (name "unconnected-(U12D-IO_L23P_3-PadU8)") (class "Default")
      (node (ref "U12") (pin "U8") (pinfunction "IO_L23P_3_U8") (pintype "passive+no_connect"))
    )
    (net (code "176") (name "unconnected-(U12D-IO_L24N_3-PadV5)") (class "Default")
      (node (ref "U12") (pin "V5") (pinfunction "IO_L24N_3_V5") (pintype "passive+no_connect"))
    )
    (net (code "177") (name "unconnected-(U12D-IO_L24P_3-PadU5)") (class "Default")
      (node (ref "U12") (pin "U5") (pinfunction "IO_L24P_3_U5") (pintype "passive+no_connect"))
    )
    (net (code "178") (name "unconnected-(U12D-IO_L25N_3-PadU9)") (class "Default")
      (node (ref "U12") (pin "U9") (pinfunction "IO_L25N_3_U9") (pintype "passive+no_connect"))
    )
    (net (code "179") (name "unconnected-(U12D-IO_L25P_3-PadT10)") (class "Default")
      (node (ref "U12") (pin "T10") (pinfunction "IO_L25P_3_T10") (pintype "passive+no_connect"))
    )
    (net (code "180") (name "unconnected-(U12D-IO_L27N_3-PadT9)") (class "Default")
      (node (ref "U12") (pin "T9") (pinfunction "IO_L27N_3_T9") (pintype "passive+no_connect"))
    )
    (net (code "181") (name "unconnected-(U12D-IO_L27P_3-PadR10)") (class "Default")
      (node (ref "U12") (pin "R10") (pinfunction "IO_L27P_3_R10") (pintype "passive+no_connect"))
    )
    (net (code "182") (name "unconnected-(U12D-IO_L28N_3-PadU3)") (class "Default")
      (node (ref "U12") (pin "U3") (pinfunction "IO_L28N_3_U3") (pintype "passive+no_connect"))
    )
    (net (code "183") (name "unconnected-(U12D-IO_L28P_3-PadU4)") (class "Default")
      (node (ref "U12") (pin "U4") (pinfunction "IO_L28P_3_U4") (pintype "passive+no_connect"))
    )
    (net (code "184") (name "unconnected-(U12D-IO_L29N_3-PadT6)") (class "Default")
      (node (ref "U12") (pin "T6") (pinfunction "IO_L29N_3_T6") (pintype "passive+no_connect"))
    )
    (net (code "185") (name "unconnected-(U12D-IO_L29P_3-PadT8)") (class "Default")
      (node (ref "U12") (pin "T8") (pinfunction "IO_L29P_3_T8") (pintype "passive+no_connect"))
    )
    (net (code "186") (name "unconnected-(U12D-IO_L30N_3-PadT4)") (class "Default")
      (node (ref "U12") (pin "T4") (pinfunction "IO_L30N_3_T4") (pintype "passive+no_connect"))
    )
    (net (code "187") (name "unconnected-(U12D-IO_L30P_3-PadR5)") (class "Default")
      (node (ref "U12") (pin "R5") (pinfunction "IO_L30P_3_R5") (pintype "passive+no_connect"))
    )
    (net (code "188") (name "unconnected-(U12D-IO_L31P_3-PadR7)") (class "Default")
      (node (ref "U12") (pin "R7") (pinfunction "IO_L31P_3_R7") (pintype "passive+no_connect"))
    )
    (net (code "189") (name "unconnected-(U12D-IO_L55N_M3A14_3-PadM4)") (class "Default")
      (node (ref "U12") (pin "M4") (pinfunction "IO_L55N_M3A14_3_M4") (pintype "passive+no_connect"))
    )
    (net (code "190") (name "unconnected-(U12D-IO_L57P_3-PadL7)") (class "Default")
      (node (ref "U12") (pin "L7") (pinfunction "IO_L57P_3_L7") (pintype "passive+no_connect"))
    )
  )
)
